# JLC_EDA.net
KiCad netlist of a schematic drawn in EasyEDA Pro
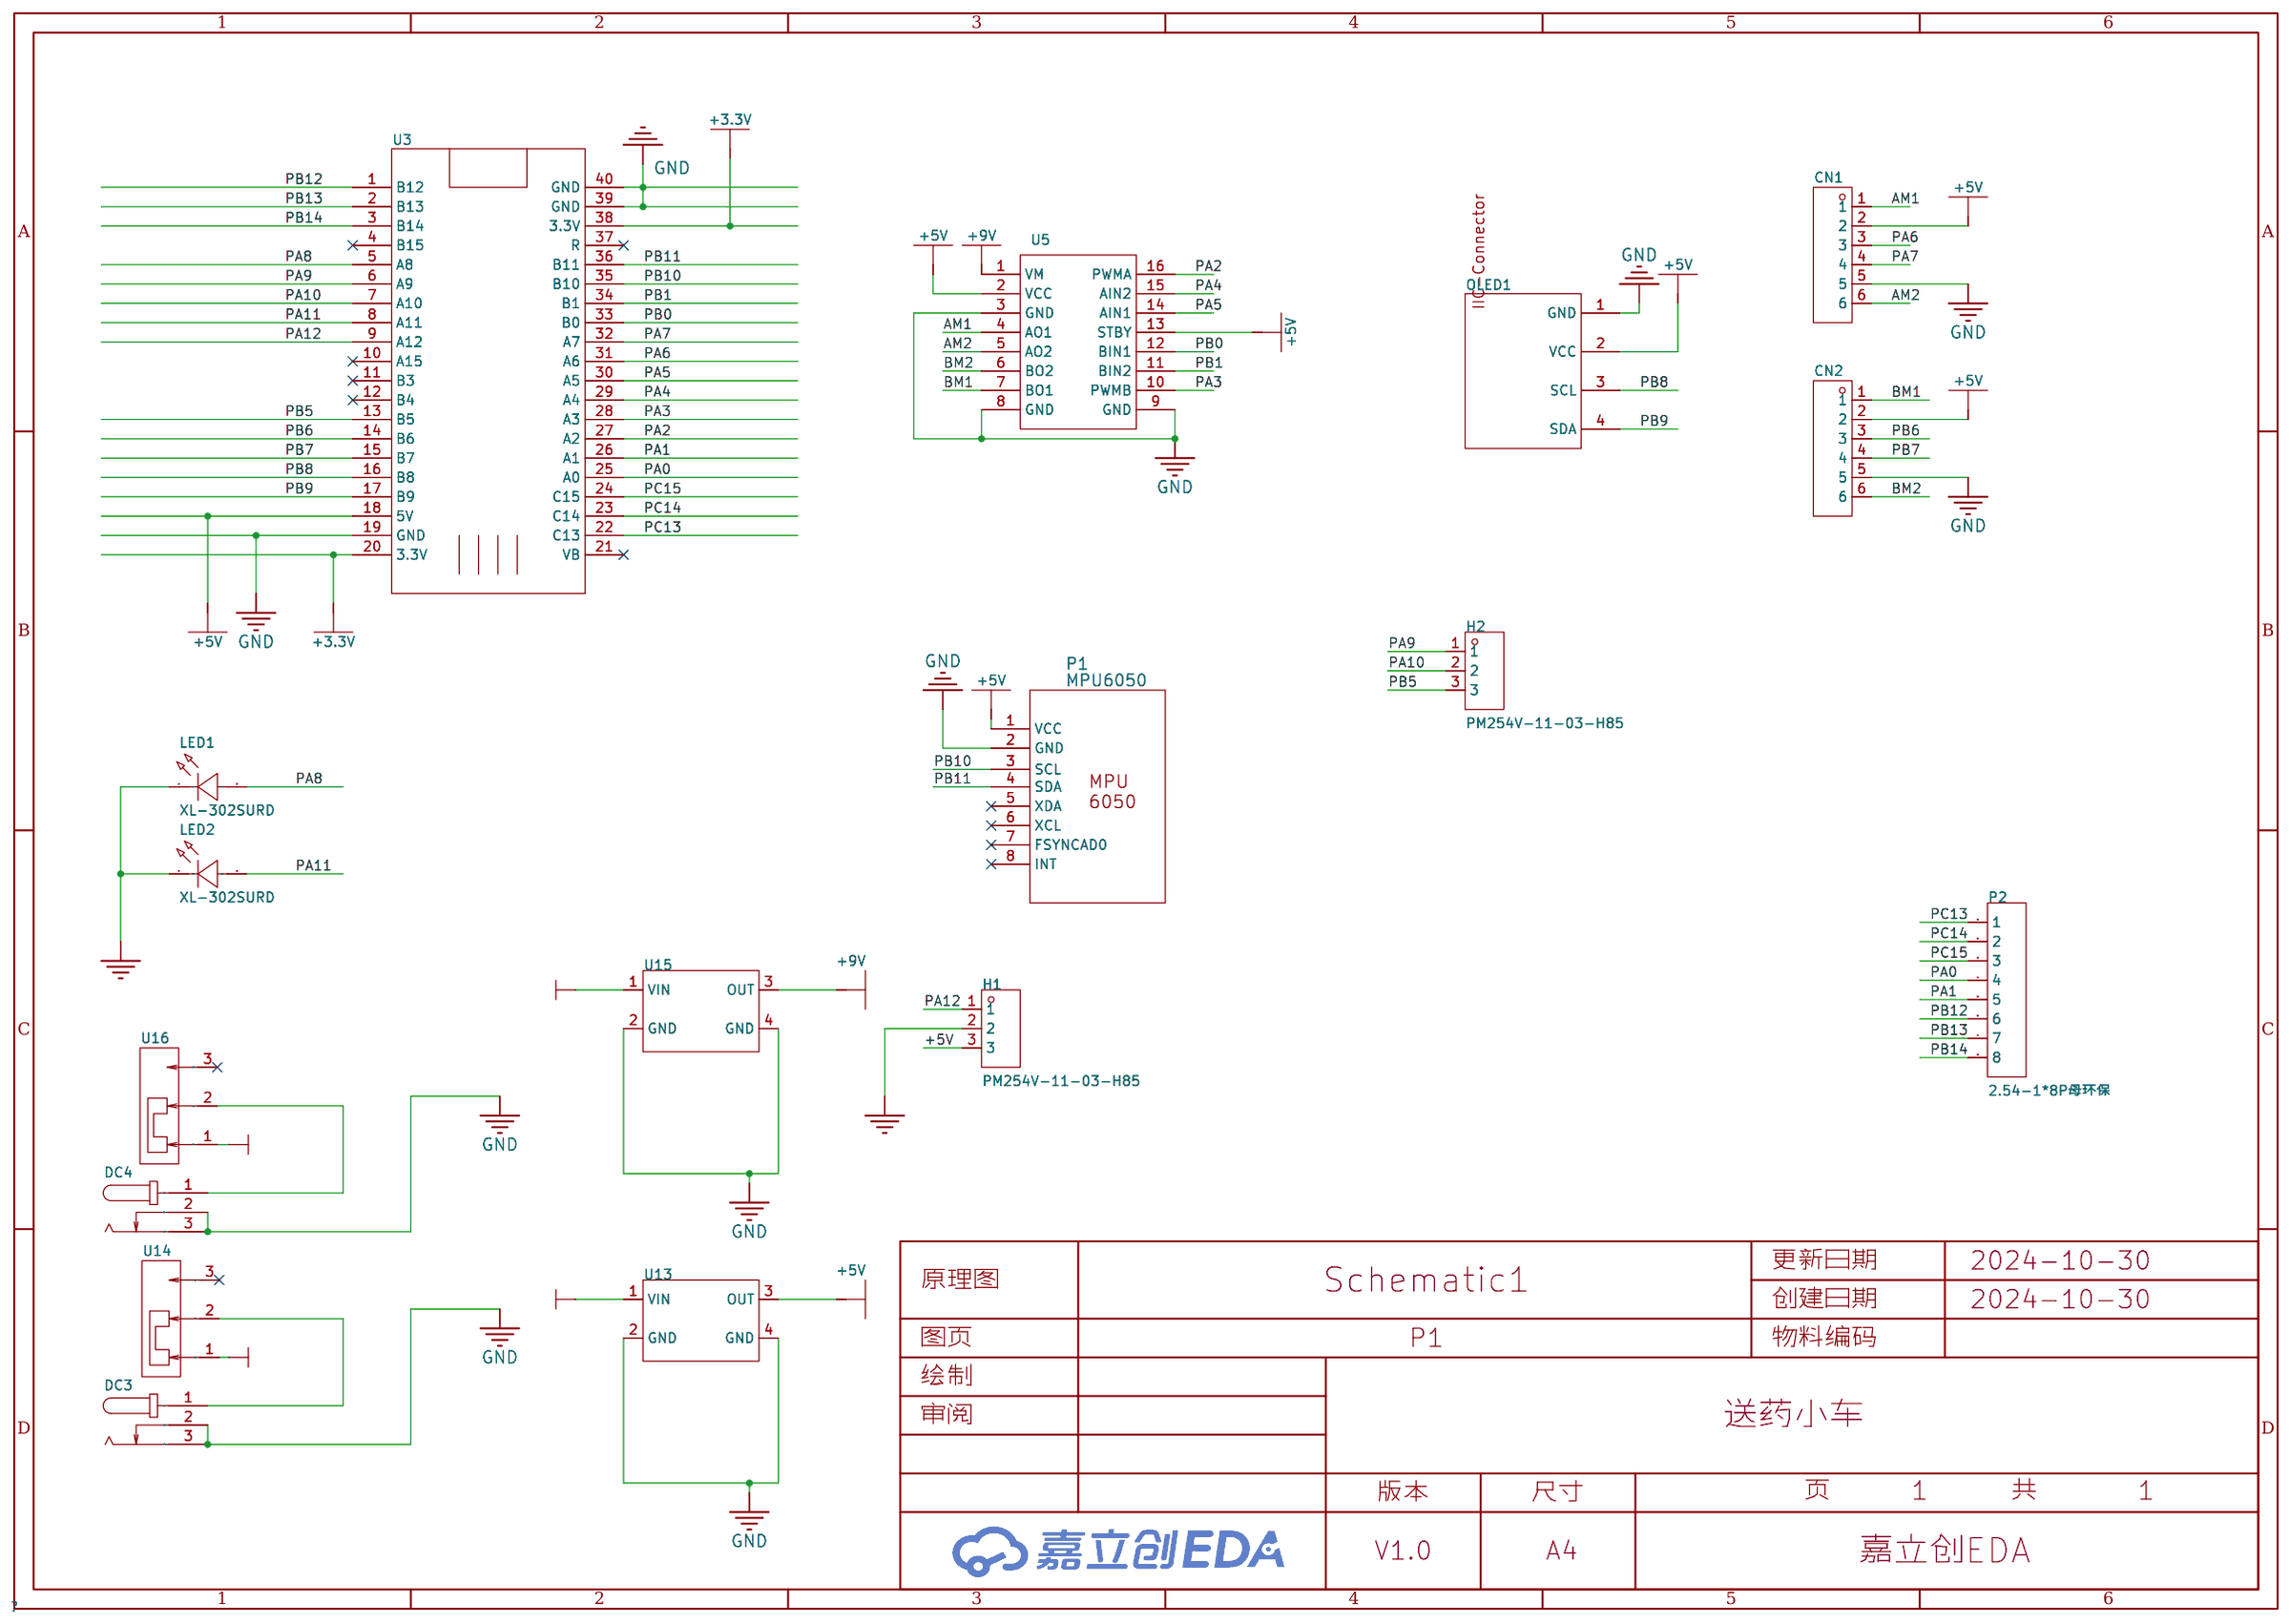
[diagram p0: schematic sheet]

(export (version "E")
  (design (tool "Eeschema 10.0.6"))
  (components
    (comp (ref "CN1")
      (value "PH2.0-6P")
      (fields (field (name "Manufacturer Part") "PH2.0-4P") (field (name "Manufacturer") "CAX(创都)"))
      (libsource (lib "easyedapro") (part "PH2.0-6P"))
    )
    (comp (ref "CN2")
      (value "PH2.0-6P")
      (fields (field (name "Manufacturer Part") "PH2.0-4P") (field (name "Manufacturer") "CAX(创都)"))
      (libsource (lib "easyedapro") (part "ph2.0-6p"))
    )
    (comp (ref "DC3")
      (value "~")
      (description "连接器类型:DC电源插座;安装方式:弯插;触点内径:-;触点外径:6.4mm;额定电流:1A;额定电压:30V;工作温度范围:-25~+70;")
      (fields
        (field (name "Manufacturer Part") "KH-DC-005-2.5")
        (field (name "Manufacturer") "kinghelm(金航标)")
      )
      (libsource (lib "easyedapro") (part "KH-DC-005-2.5"))
    )
    (comp (ref "DC4")
      (value "~")
      (description "连接器类型:DC电源插座;安装方式:弯插;触点内径:-;触点外径:6.4mm;额定电流:1A;额定电压:30V;工作温度范围:-25~+70;")
      (fields
        (field (name "Manufacturer Part") "KH-DC-005-2.5")
        (field (name "Manufacturer") "kinghelm(金航标)")
      )
      (libsource (lib "easyedapro") (part "KH-DC-005-2.5"))
    )
    (comp (ref "H1")
      (value "PM254V-11-03-H85")
      (footprint "easyedapro:HDR-TH_3P-P2.54-V-F")
      (description "插孔结构:1x3P;间距:2.54mm;行距:-;安装类型:直插;排数:单排;总孔位数:3P;塑高:-;触头材质:黄铜;触头镀层:-;")
      (fields (field (name "Manufacturer") "XFCN(兴飞)"))
      (libsource (lib "easyedapro") (part "PM254V-11-03-H85"))
    )
    (comp (ref "H2")
      (value "PM254V-11-03-H85")
      (footprint "easyedapro:HDR-TH_3P-P2.54-V-F")
      (description "插孔结构:1x3P;间距:2.54mm;行距:-;安装类型:直插;排数:单排;总孔位数:3P;塑高:-;触头材质:黄铜;触头镀层:-;")
      (fields (field (name "Manufacturer") "XFCN(兴飞)"))
      (libsource (lib "easyedapro") (part "PM254V-11-03-H85"))
    )
    (comp (ref "LED1")
      (value "XL-302SURD")
      (footprint "easyedapro:LED-TH_BD3.8-P2.54-RD")
      (fields (field (name "Manufacturer") "XINGLIGHT(成兴光)"))
      (libsource (lib "easyedapro") (part "XL-302SURD"))
    )
    (comp (ref "LED2")
      (value "XL-302SURD")
      (footprint "easyedapro:LED-TH_BD3.8-P2.54-RD")
      (fields (field (name "Manufacturer") "XINGLIGHT(成兴光)"))
      (libsource (lib "easyedapro") (part "XL-302SURD"))
    )
    (comp (ref "OLED1")
      (value "~")
      (fields (field (name "Manufacturer Part") "0.96OLED_4P_MODULE_JX"))
      (libsource (lib "easyedapro") (part "0.96OLED_4P_MODULE_JX"))
    )
    (comp (ref "P1") (value "MPU6050") (libsource (lib "easyedapro") (part "MPU6050")))
    (comp (ref "P2")
      (value "2.54-1*8P母环保")
      (footprint "easyedapro:HDR-TH_8P-P2.54-V-F-1")
      (description "插孔结构:1x8P;间距:2.54mm;行距:-;安装类型:直插;排数:单排;总孔位数:8P;塑高:-;触头材质:-;触头镀层:-;")
      (fields (field (name "Manufacturer") "BOOMELE(博穆精密)"))
      (libsource (lib "easyedapro") (part "Header-Female-2.54_1x8"))
    )
    (comp (ref "U3") (value "~") (libsource (lib "easyedapro") (part "STM32F103C8T6核心板")))
    (comp (ref "U5") (value "~") (libsource (lib "easyedapro") (part "TB6612FNG模块")))
    (comp (ref "U13")
      (value "~")
      (footprint "easyedapro:MP1584模块")
      (libsource (lib "easyedapro") (part "MP1584模块"))
    )
    (comp (ref "U14")
      (value "SS-12D10-G5")
      (footprint "easyedapro:SW-TH_SS-12D10-G050")
      (description "电路结构:单刀双掷;安装方式:直插;开关颜色:黑色;滑钮形状:矩形柱状;引脚样式:PC引脚;开关长度:12.7mm;开关宽度:6.7mm;开关高度:11.3mm;")
      (fields (field (name "Manufacturer") "DEALON(德艺隆)"))
      (libsource (lib "easyedapro") (part "SS-12D10-G5"))
    )
    (comp (ref "U15")
      (value "~")
      (footprint "easyedapro:MP1584模块")
      (libsource (lib "easyedapro") (part "MP1584模块"))
    )
    (comp (ref "U16")
      (value "SS-12D10-G5")
      (footprint "easyedapro:SW-TH_SS-12D10-G050")
      (description "电路结构:单刀双掷;安装方式:直插;开关颜色:黑色;滑钮形状:矩形柱状;引脚样式:PC引脚;开关长度:12.7mm;开关宽度:6.7mm;开关高度:11.3mm;")
      (fields (field (name "Manufacturer") "DEALON(德艺隆)"))
      (libsource (lib "easyedapro") (part "SS-12D10-G5"))
    )
  )
  (nets
    (net (code "1") (name "+3.3V") (class "Default")
      (node (ref "U3") (pin "20") (pinfunction "3.3V_20") (pintype "unspecified"))
      (node (ref "U3") (pin "38") (pinfunction "3.3V_38") (pintype "unspecified"))
    )
    (net (code "2") (name "+5V") (class "Default")
      (node (ref "CN1") (pin "2") (pinfunction "2_2") (pintype "input"))
      (node (ref "CN2") (pin "2") (pinfunction "2_2") (pintype "input"))
      (node (ref "H1") (pin "3") (pinfunction "3_3") (pintype "unspecified"))
      (node (ref "OLED1") (pin "2") (pinfunction "VCC_2") (pintype "input"))
      (node (ref "P1") (pin "1") (pinfunction "VCC_1") (pintype "input"))
      (node (ref "U13") (pin "3") (pinfunction "OUT_3") (pintype "unspecified"))
      (node (ref "U3") (pin "18") (pinfunction "5V_18") (pintype "unspecified"))
      (node (ref "U5") (pin "13") (pinfunction "STBY_13") (pintype "input"))
      (node (ref "U5") (pin "2") (pinfunction "VCC_2") (pintype "input"))
    )
    (net (code "3") (name "+9V") (class "Default")
      (node (ref "U15") (pin "3") (pinfunction "OUT_3") (pintype "unspecified"))
      (node (ref "U5") (pin "1") (pinfunction "VM_1") (pintype "input"))
    )
    (net (code "4") (name "+12.5V") (class "Default")
      (node (ref "U15") (pin "1") (pinfunction "VIN_1") (pintype "unspecified"))
      (node (ref "U16") (pin "1") (pinfunction "1_1") (pintype "input"))
    )
    (net (code "5") (name "+12V") (class "Default")
      (node (ref "U13") (pin "1") (pinfunction "VIN_1") (pintype "unspecified"))
      (node (ref "U14") (pin "1") (pinfunction "1_1") (pintype "input"))
    )
    (net (code "6") (name "/AM1") (class "Default")
      (node (ref "CN1") (pin "1") (pinfunction "1_1") (pintype "input"))
      (node (ref "U5") (pin "4") (pinfunction "AO1_4") (pintype "input"))
    )
    (net (code "7") (name "/AM2") (class "Default")
      (node (ref "CN1") (pin "6") (pinfunction "6_6") (pintype "input"))
      (node (ref "U5") (pin "5") (pinfunction "AO2_5") (pintype "input"))
    )
    (net (code "8") (name "/BM1") (class "Default")
      (node (ref "CN2") (pin "1") (pinfunction "1_1") (pintype "input"))
      (node (ref "U5") (pin "7") (pinfunction "BO1_7") (pintype "input"))
    )
    (net (code "9") (name "/BM2") (class "Default")
      (node (ref "CN2") (pin "6") (pinfunction "6_6") (pintype "input"))
      (node (ref "U5") (pin "6") (pinfunction "BO2_6") (pintype "input"))
    )
    (net (code "10") (name "/PA0") (class "Default")
      (node (ref "P2") (pin "4") (pinfunction "4_4") (pintype "input"))
      (node (ref "U3") (pin "25") (pinfunction "A0_25") (pintype "unspecified"))
    )
    (net (code "11") (name "/PA1") (class "Default")
      (node (ref "P2") (pin "5") (pinfunction "5_5") (pintype "input"))
      (node (ref "U3") (pin "26") (pinfunction "A1_26") (pintype "unspecified"))
    )
    (net (code "12") (name "/PA2") (class "Default")
      (node (ref "U3") (pin "27") (pinfunction "A2_27") (pintype "unspecified"))
      (node (ref "U5") (pin "16") (pinfunction "PWMA_16") (pintype "input"))
    )
    (net (code "13") (name "/PA3") (class "Default")
      (node (ref "U3") (pin "28") (pinfunction "A3_28") (pintype "unspecified"))
      (node (ref "U5") (pin "10") (pinfunction "PWMB_10") (pintype "input"))
    )
    (net (code "14") (name "/PA4") (class "Default")
      (node (ref "U3") (pin "29") (pinfunction "A4_29") (pintype "unspecified"))
      (node (ref "U5") (pin "15") (pinfunction "AIN2_15") (pintype "input"))
    )
    (net (code "15") (name "/PA5") (class "Default")
      (node (ref "U3") (pin "30") (pinfunction "A5_30") (pintype "unspecified"))
      (node (ref "U5") (pin "14") (pinfunction "AIN1_14") (pintype "input"))
    )
    (net (code "16") (name "/PA6") (class "Default")
      (node (ref "CN1") (pin "3") (pinfunction "3_3") (pintype "input"))
      (node (ref "U3") (pin "31") (pinfunction "A6_31") (pintype "unspecified"))
    )
    (net (code "17") (name "/PA7") (class "Default")
      (node (ref "CN1") (pin "4") (pinfunction "4_4") (pintype "input"))
      (node (ref "U3") (pin "32") (pinfunction "A7_32") (pintype "unspecified"))
    )
    (net (code "18") (name "/PA8") (class "Default")
      (node (ref "LED1") (pin "2") (pinfunction "A_2") (pintype "unspecified"))
      (node (ref "U3") (pin "5") (pinfunction "A8_5") (pintype "unspecified"))
    )
    (net (code "19") (name "/PA9") (class "Default")
      (node (ref "H2") (pin "1") (pinfunction "1_1") (pintype "unspecified"))
      (node (ref "U3") (pin "6") (pinfunction "A9_6") (pintype "unspecified"))
    )
    (net (code "20") (name "/PA10") (class "Default")
      (node (ref "H2") (pin "2") (pinfunction "2_2") (pintype "unspecified"))
      (node (ref "U3") (pin "7") (pinfunction "A10_7") (pintype "unspecified"))
    )
    (net (code "21") (name "/PA11") (class "Default")
      (node (ref "LED2") (pin "2") (pinfunction "A_2") (pintype "unspecified"))
      (node (ref "U3") (pin "8") (pinfunction "A11_8") (pintype "unspecified"))
    )
    (net (code "22") (name "/PA12") (class "Default")
      (node (ref "H1") (pin "1") (pinfunction "1_1") (pintype "unspecified"))
      (node (ref "U3") (pin "9") (pinfunction "A12_9") (pintype "unspecified"))
    )
    (net (code "23") (name "/PB0") (class "Default")
      (node (ref "U3") (pin "33") (pinfunction "B0_33") (pintype "unspecified"))
      (node (ref "U5") (pin "12") (pinfunction "BIN1_12") (pintype "input"))
    )
    (net (code "24") (name "/PB1") (class "Default")
      (node (ref "U3") (pin "34") (pinfunction "B1_34") (pintype "unspecified"))
      (node (ref "U5") (pin "11") (pinfunction "BIN2_11") (pintype "input"))
    )
    (net (code "25") (name "/PB5") (class "Default")
      (node (ref "H2") (pin "3") (pinfunction "3_3") (pintype "unspecified"))
      (node (ref "U3") (pin "13") (pinfunction "B5_13") (pintype "unspecified"))
    )
    (net (code "26") (name "/PB6") (class "Default")
      (node (ref "CN2") (pin "3") (pinfunction "3_3") (pintype "input"))
      (node (ref "U3") (pin "14") (pinfunction "B6_14") (pintype "unspecified"))
    )
    (net (code "27") (name "/PB7") (class "Default")
      (node (ref "CN2") (pin "4") (pinfunction "4_4") (pintype "input"))
      (node (ref "U3") (pin "15") (pinfunction "B7_15") (pintype "unspecified"))
    )
    (net (code "28") (name "/PB8") (class "Default")
      (node (ref "OLED1") (pin "3") (pinfunction "SCL_3") (pintype "input"))
      (node (ref "U3") (pin "16") (pinfunction "B8_16") (pintype "unspecified"))
    )
    (net (code "29") (name "/PB9") (class "Default")
      (node (ref "OLED1") (pin "4") (pinfunction "SDA_4") (pintype "input"))
      (node (ref "U3") (pin "17") (pinfunction "B9_17") (pintype "unspecified"))
    )
    (net (code "30") (name "/PB10") (class "Default")
      (node (ref "P1") (pin "3") (pinfunction "SCL_3") (pintype "input"))
      (node (ref "U3") (pin "35") (pinfunction "B10_35") (pintype "unspecified"))
    )
    (net (code "31") (name "/PB11") (class "Default")
      (node (ref "P1") (pin "4") (pinfunction "SDA_4") (pintype "input"))
      (node (ref "U3") (pin "36") (pinfunction "B11_36") (pintype "unspecified"))
    )
    (net (code "32") (name "/PB12") (class "Default")
      (node (ref "P2") (pin "6") (pinfunction "6_6") (pintype "input"))
      (node (ref "U3") (pin "1") (pinfunction "B12_1") (pintype "unspecified"))
    )
    (net (code "33") (name "/PB13") (class "Default")
      (node (ref "P2") (pin "7") (pinfunction "7_7") (pintype "input"))
      (node (ref "U3") (pin "2") (pinfunction "B13_2") (pintype "unspecified"))
    )
    (net (code "34") (name "/PB14") (class "Default")
      (node (ref "P2") (pin "8") (pinfunction "8_8") (pintype "input"))
      (node (ref "U3") (pin "3") (pinfunction "B14_3") (pintype "unspecified"))
    )
    (net (code "35") (name "/PC13") (class "Default")
      (node (ref "P2") (pin "1") (pinfunction "1_1") (pintype "input"))
      (node (ref "U3") (pin "22") (pinfunction "C13_22") (pintype "unspecified"))
    )
    (net (code "36") (name "/PC14") (class "Default")
      (node (ref "P2") (pin "2") (pinfunction "2_2") (pintype "input"))
      (node (ref "U3") (pin "23") (pinfunction "C14_23") (pintype "unspecified"))
    )
    (net (code "37") (name "/PC15") (class "Default")
      (node (ref "P2") (pin "3") (pinfunction "3_3") (pintype "input"))
      (node (ref "U3") (pin "24") (pinfunction "C15_24") (pintype "unspecified"))
    )
    (net (code "38") (name "GND") (class "Default")
      (node (ref "CN1") (pin "5") (pinfunction "5_5") (pintype "input"))
      (node (ref "CN2") (pin "5") (pinfunction "5_5") (pintype "input"))
      (node (ref "DC3") (pin "2") (pinfunction "2_2") (pintype "input"))
      (node (ref "DC3") (pin "3") (pinfunction "3_3") (pintype "input"))
      (node (ref "DC4") (pin "2") (pinfunction "2_2") (pintype "input"))
      (node (ref "DC4") (pin "3") (pinfunction "3_3") (pintype "input"))
      (node (ref "H1") (pin "2") (pinfunction "2_2") (pintype "unspecified"))
      (node (ref "LED1") (pin "1") (pinfunction "K_1") (pintype "unspecified"))
      (node (ref "LED2") (pin "1") (pinfunction "K_1") (pintype "unspecified"))
      (node (ref "OLED1") (pin "1") (pinfunction "GND_1") (pintype "input"))
      (node (ref "P1") (pin "2") (pinfunction "GND_2") (pintype "input"))
      (node (ref "U13") (pin "2") (pinfunction "GND_2") (pintype "unspecified"))
      (node (ref "U13") (pin "4") (pinfunction "GND_4") (pintype "unspecified"))
      (node (ref "U15") (pin "2") (pinfunction "GND_2") (pintype "unspecified"))
      (node (ref "U15") (pin "4") (pinfunction "GND_4") (pintype "unspecified"))
      (node (ref "U3") (pin "19") (pinfunction "GND_19") (pintype "unspecified"))
      (node (ref "U3") (pin "39") (pinfunction "GND_39") (pintype "unspecified"))
      (node (ref "U3") (pin "40") (pinfunction "GND_40") (pintype "unspecified"))
      (node (ref "U5") (pin "3") (pinfunction "GND_3") (pintype "input"))
      (node (ref "U5") (pin "8") (pinfunction "GND_8") (pintype "input"))
      (node (ref "U5") (pin "9") (pinfunction "GND_9") (pintype "input"))
    )
    (net (code "39") (name "Net-(DC3-Pad1)") (class "Default")
      (node (ref "DC3") (pin "1") (pinfunction "1_1") (pintype "input"))
      (node (ref "U14") (pin "2") (pinfunction "2_2") (pintype "input"))
    )
    (net (code "40") (name "Net-(DC4-Pad1)") (class "Default")
      (node (ref "DC4") (pin "1") (pinfunction "1_1") (pintype "input"))
      (node (ref "U16") (pin "2") (pinfunction "2_2") (pintype "input"))
    )
    (net (code "41") (name "unconnected-(P1-FSYNCAD0-Pad7)") (class "Default")
      (node (ref "P1") (pin "7") (pinfunction "FSYNCAD0_7") (pintype "input+no_connect"))
    )
    (net (code "42") (name "unconnected-(P1-INT-Pad8)") (class "Default")
      (node (ref "P1") (pin "8") (pinfunction "INT_8") (pintype "input+no_connect"))
    )
    (net (code "43") (name "unconnected-(P1-XCL-Pad6)") (class "Default")
      (node (ref "P1") (pin "6") (pinfunction "XCL_6") (pintype "input+no_connect"))
    )
    (net (code "44") (name "unconnected-(P1-XDA-Pad5)") (class "Default")
      (node (ref "P1") (pin "5") (pinfunction "XDA_5") (pintype "input+no_connect"))
    )
    (net (code "45") (name "unconnected-(U3-A15-Pad10)") (class "Default")
      (node (ref "U3") (pin "10") (pinfunction "A15_10") (pintype "unspecified+no_connect"))
    )
    (net (code "46") (name "unconnected-(U3-B3-Pad11)") (class "Default")
      (node (ref "U3") (pin "11") (pinfunction "B3_11") (pintype "unspecified+no_connect"))
    )
    (net (code "47") (name "unconnected-(U3-B4-Pad12)") (class "Default")
      (node (ref "U3") (pin "12") (pinfunction "B4_12") (pintype "unspecified+no_connect"))
    )
    (net (code "48") (name "unconnected-(U3-B15-Pad4)") (class "Default")
      (node (ref "U3") (pin "4") (pinfunction "B15_4") (pintype "unspecified+no_connect"))
    )
    (net (code "49") (name "unconnected-(U3-R-Pad37)") (class "Default")
      (node (ref "U3") (pin "37") (pinfunction "R_37") (pintype "unspecified+no_connect"))
    )
    (net (code "50") (name "unconnected-(U3-VB-Pad21)") (class "Default")
      (node (ref "U3") (pin "21") (pinfunction "VB_21") (pintype "unspecified+no_connect"))
    )
    (net (code "51") (name "unconnected-(U14-Pad3)") (class "Default")
      (node (ref "U14") (pin "3") (pinfunction "3_3") (pintype "input+no_connect"))
    )
    (net (code "52") (name "unconnected-(U16-Pad3)") (class "Default")
      (node (ref "U16") (pin "3") (pinfunction "3_3") (pintype "input+no_connect"))
    )
  )
)
